# 16P1D_EDA.net
KiCad netlist of a schematic drawn in EasyEDA Pro
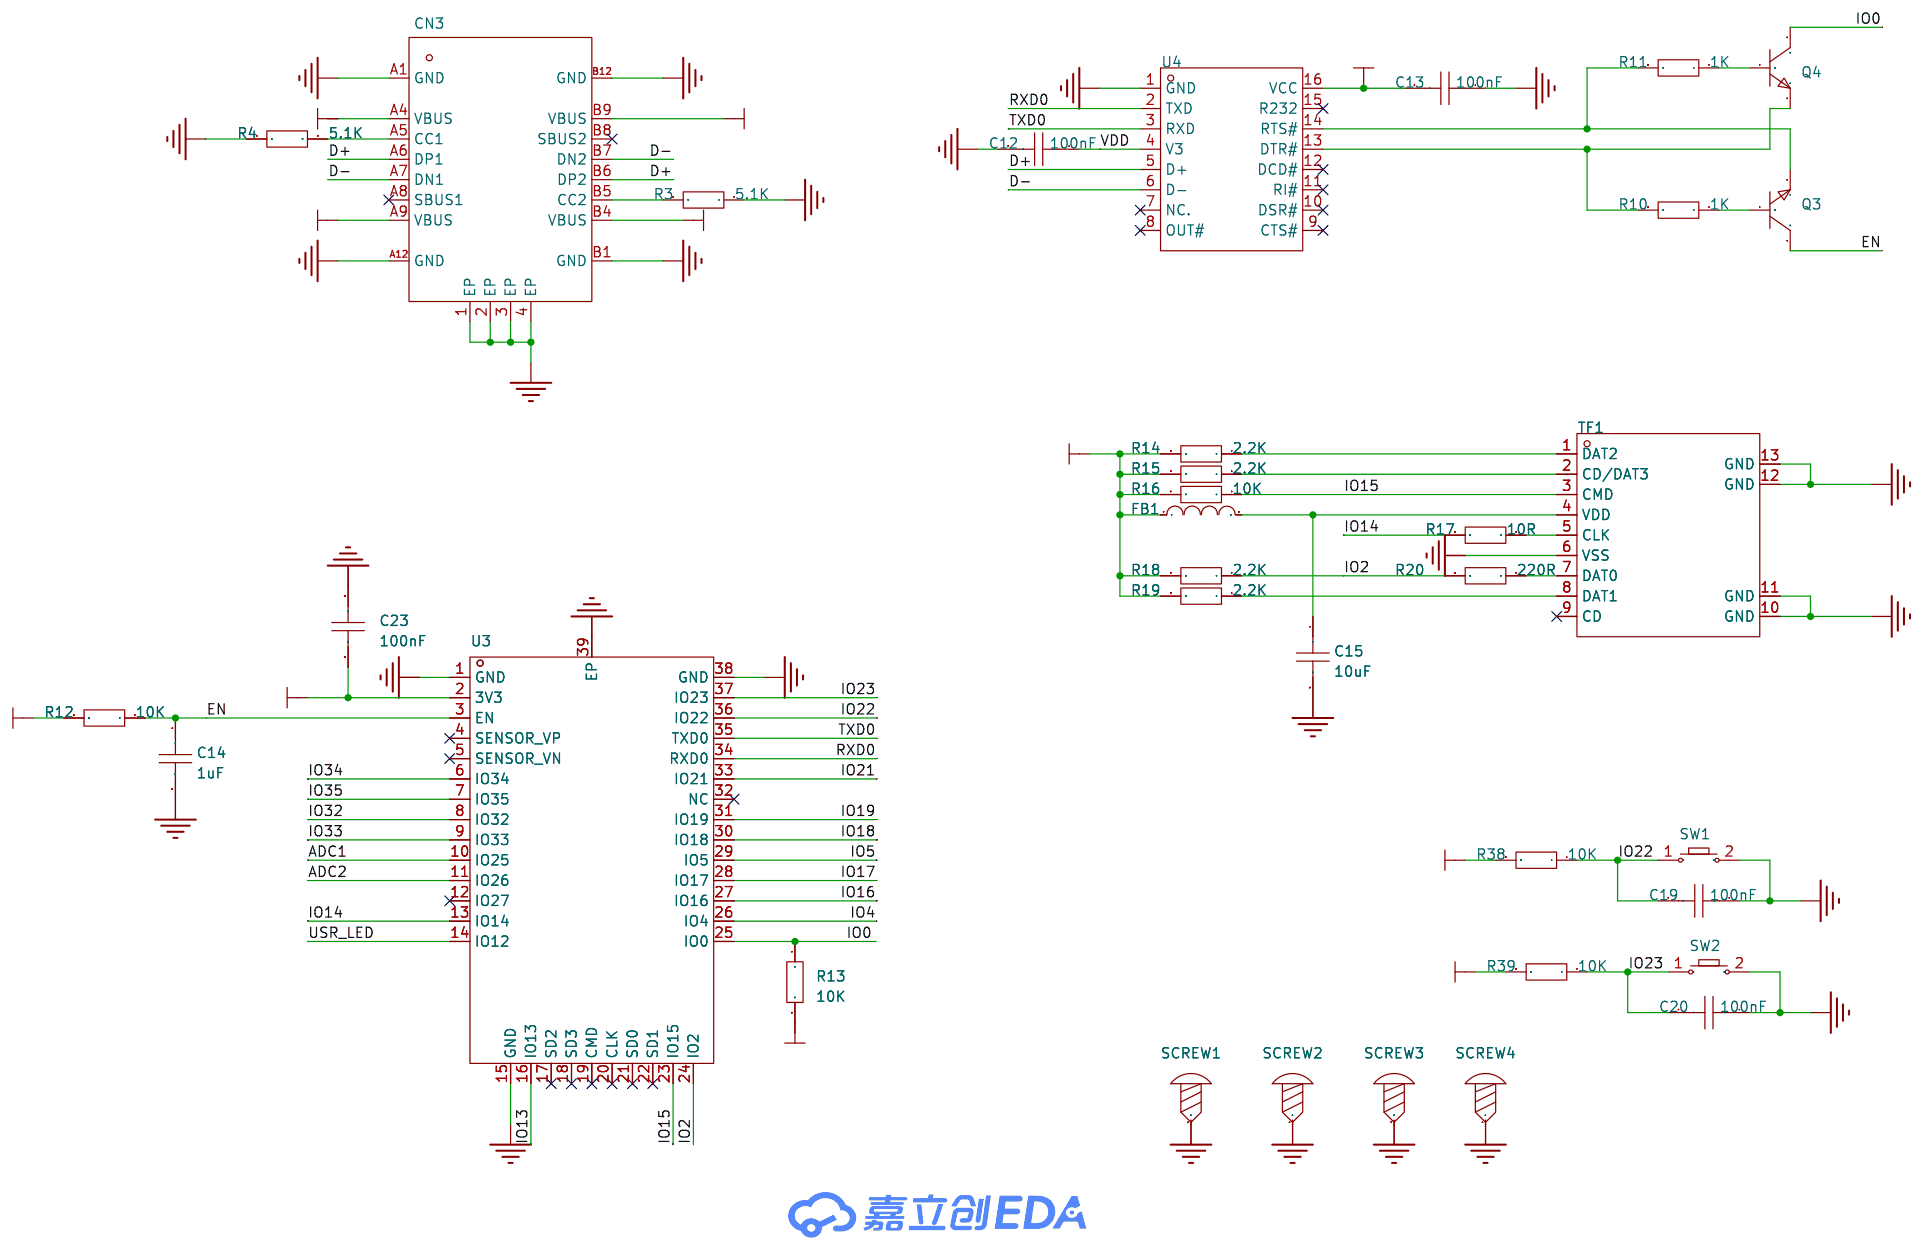
[diagram p0: ESP32]
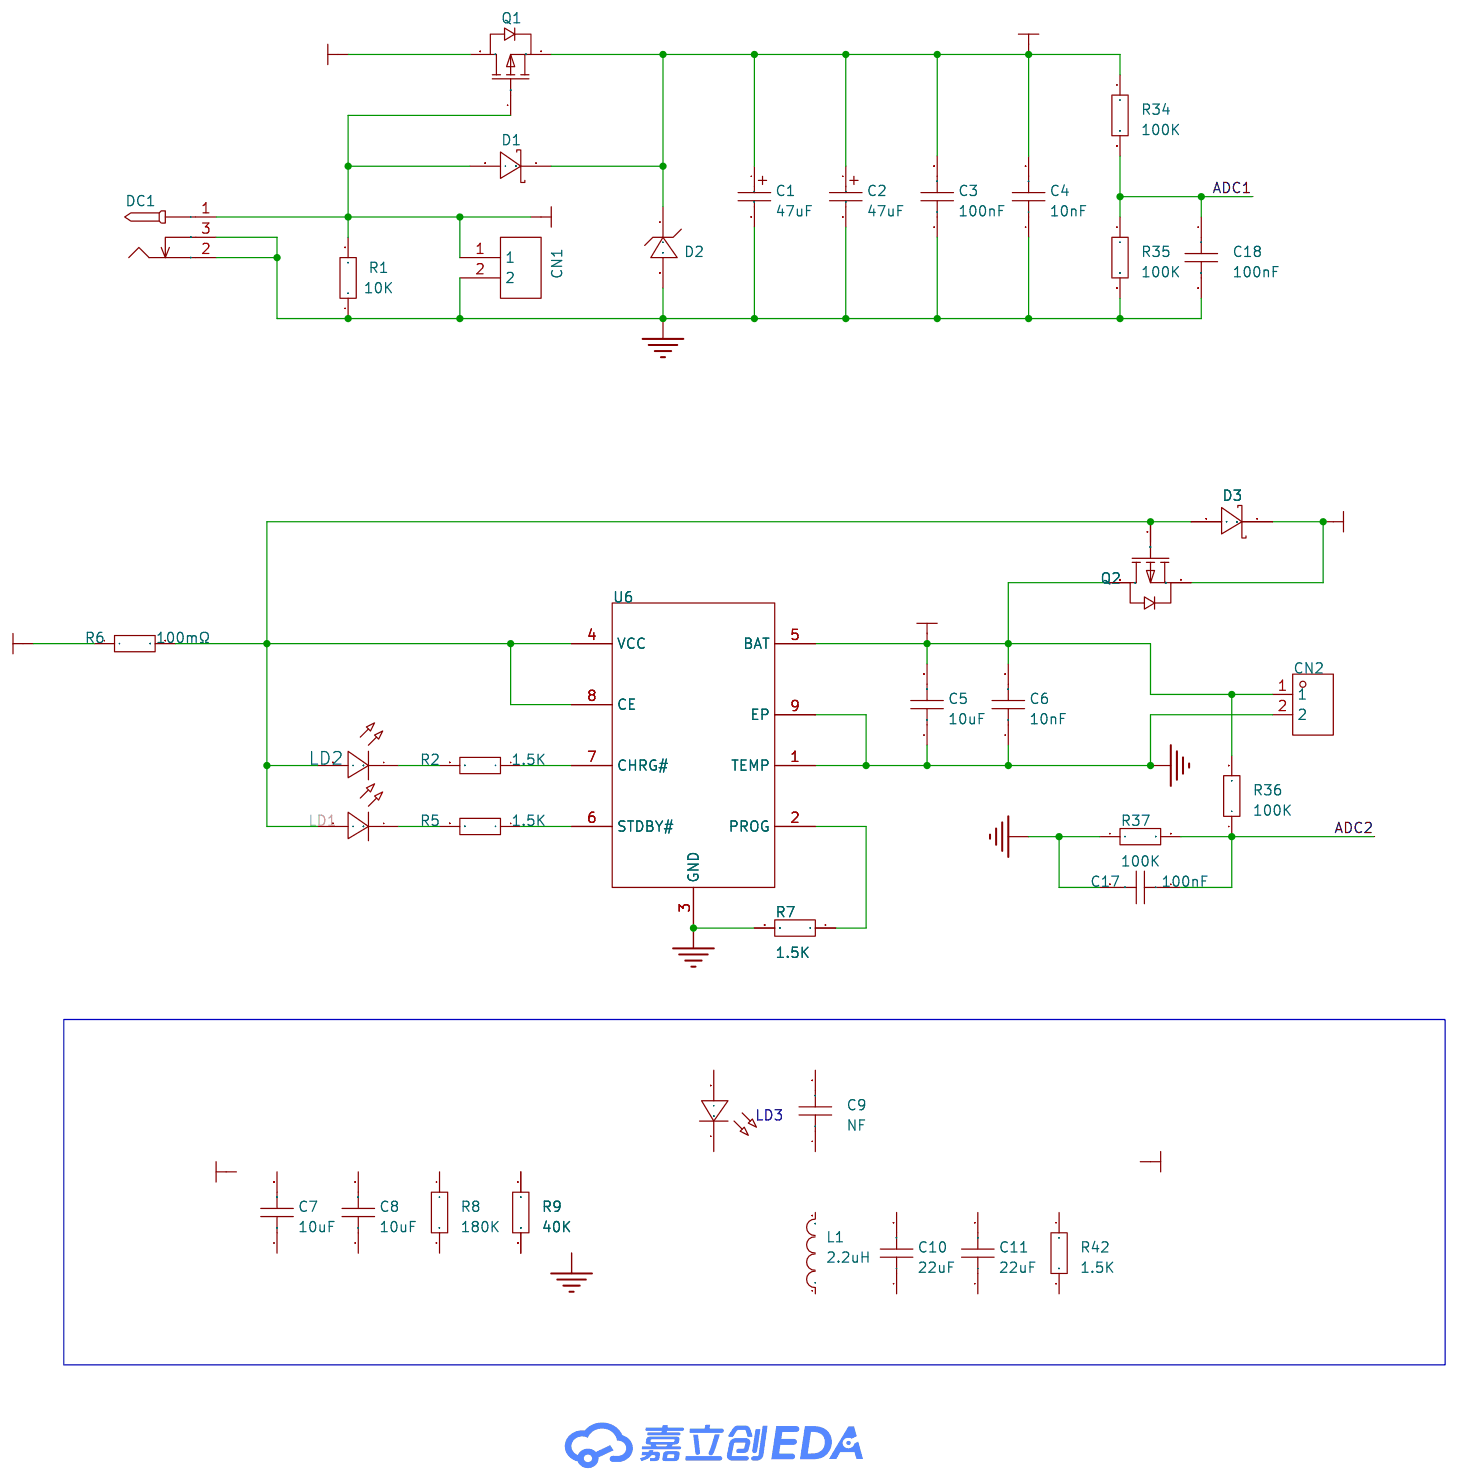
[diagram p1: DC]
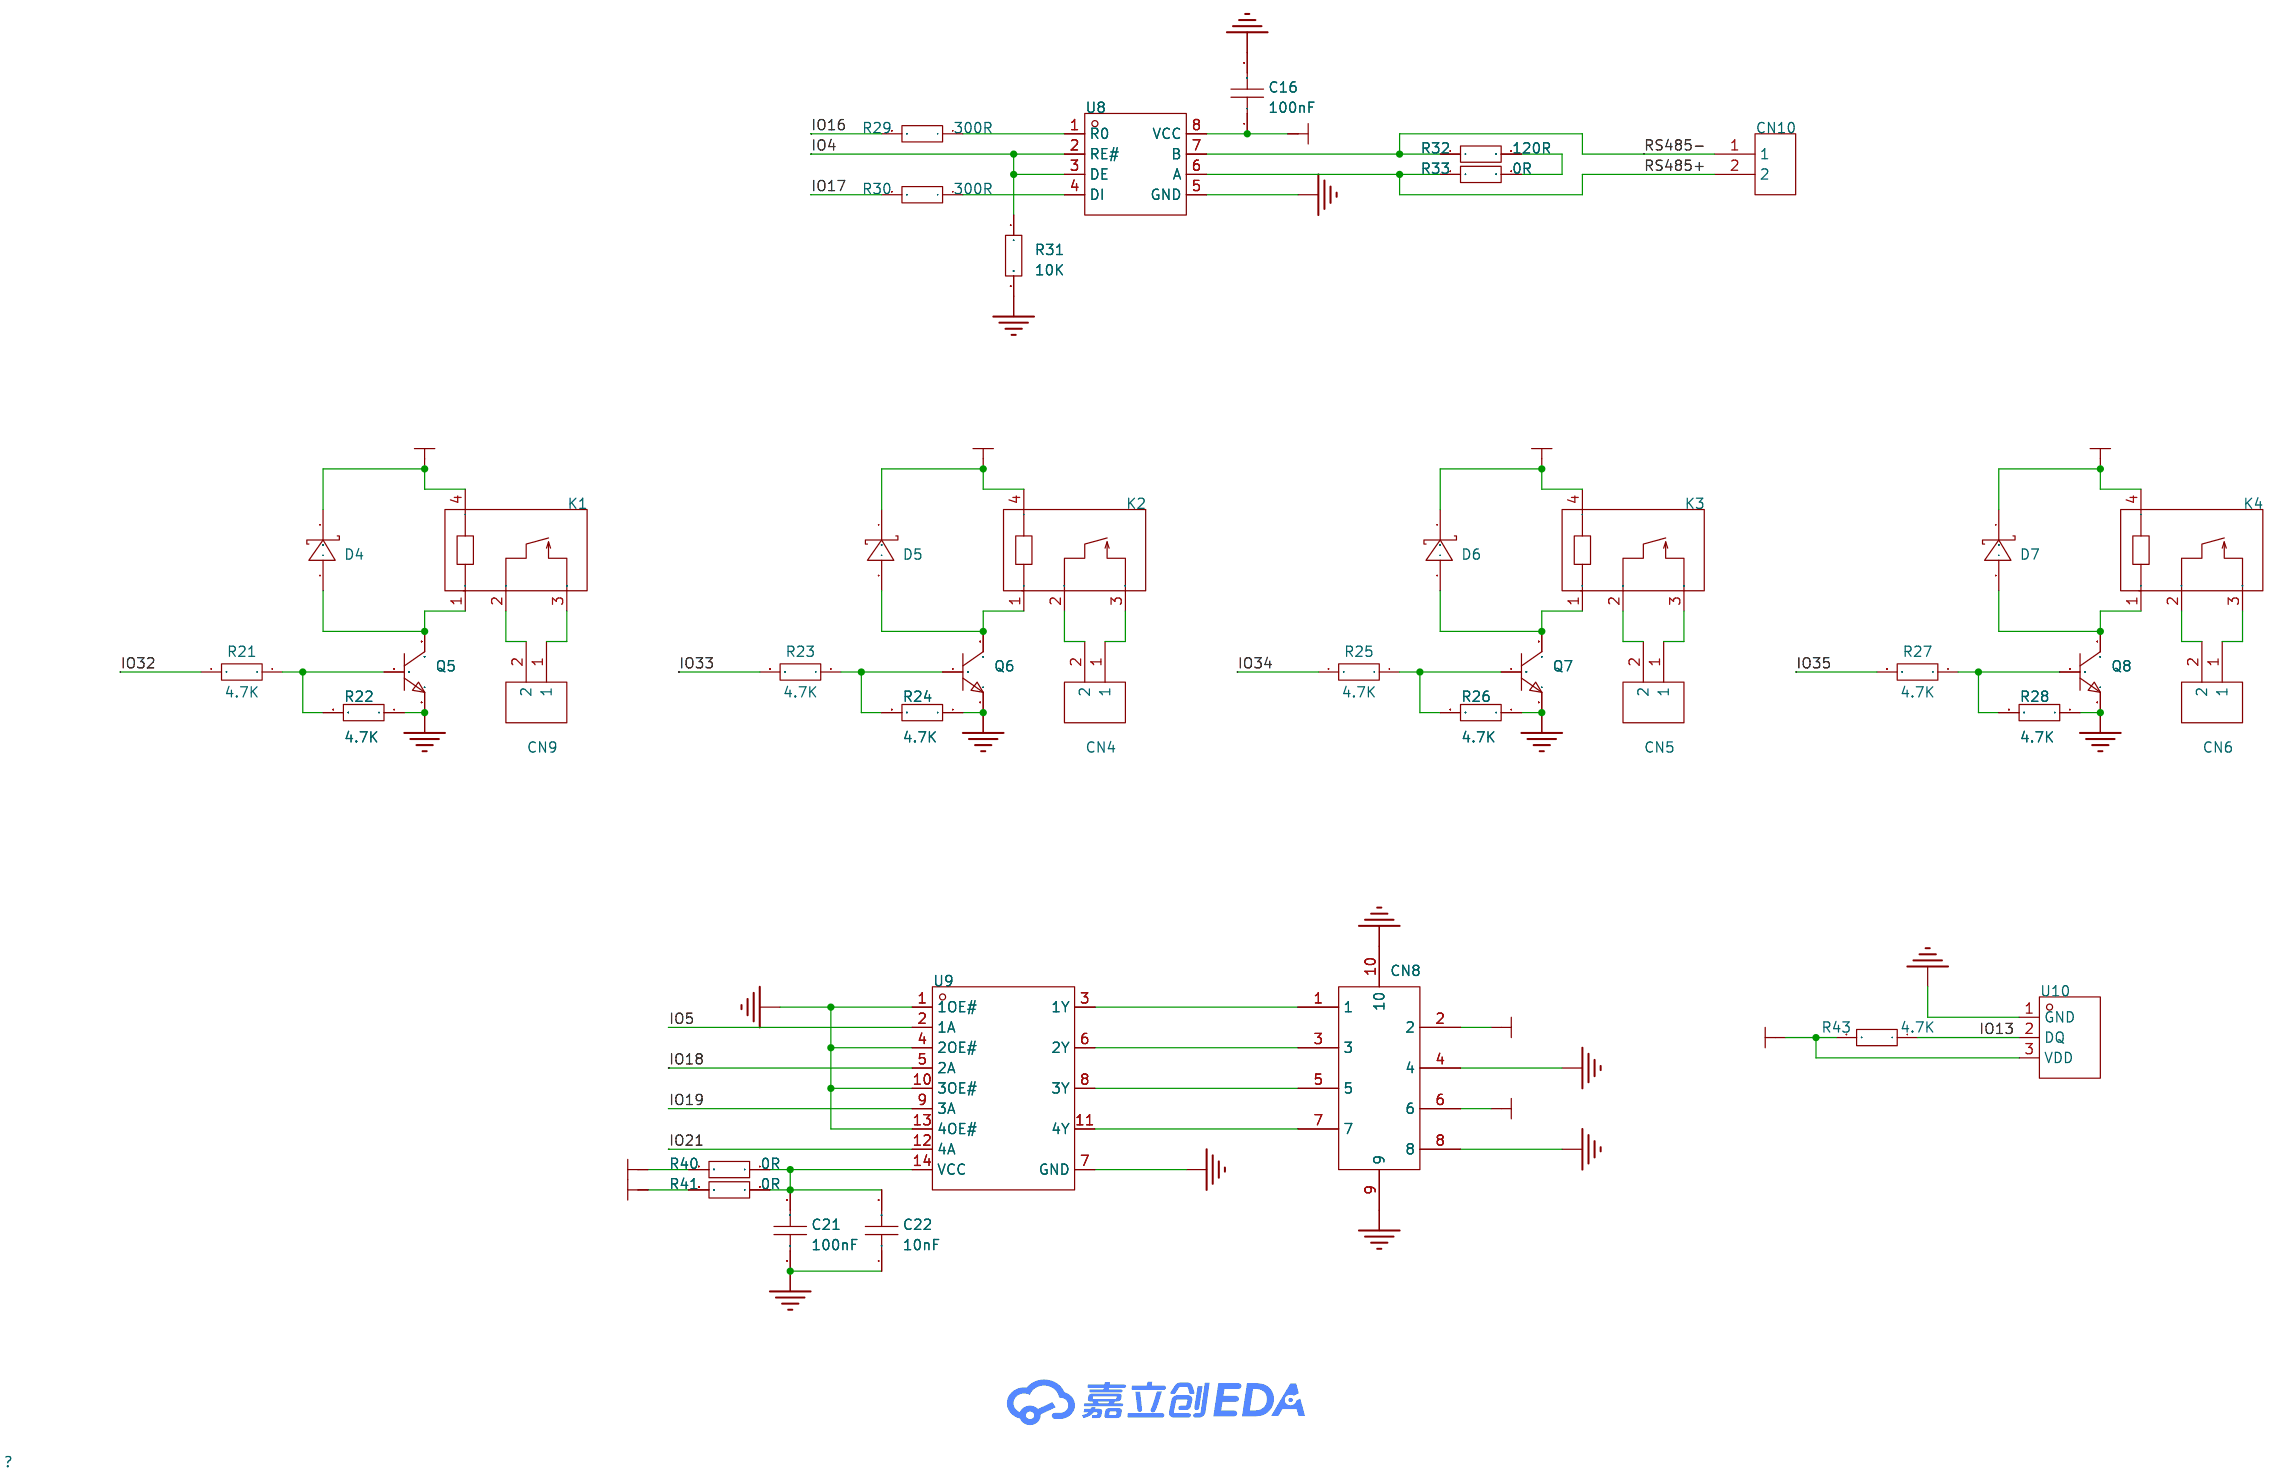
[diagram p2: RELAY]

(export (version "E")
  (design (tool "Eeschema 10.0.6"))
  (components
    (comp (ref "C12")
      (value "100nF")
      (footprint "easyedapro:C0805")
      (libsource (lib "easyedapro") (part "CapAcitance"))
    )
    (comp (ref "C13")
      (value "100nF")
      (footprint "easyedapro:C0805")
      (libsource (lib "easyedapro") (part "CapAcitance"))
    )
    (comp (ref "C14")
      (value "1uF")
      (footprint "easyedapro:C0805")
      (libsource (lib "easyedapro") (part "CapAcitance"))
    )
    (comp (ref "C15")
      (value "10uF")
      (footprint "easyedapro:C0805")
      (libsource (lib "easyedapro") (part "CapAcitance"))
    )
    (comp (ref "C19")
      (value "100nF")
      (footprint "easyedapro:C0805")
      (libsource (lib "easyedapro") (part "CapAcitance"))
    )
    (comp (ref "C20")
      (value "100nF")
      (footprint "easyedapro:C0805")
      (libsource (lib "easyedapro") (part "CapAcitance"))
    )
    (comp (ref "C23")
      (value "100nF")
      (footprint "easyedapro:C0805")
      (libsource (lib "easyedapro") (part "CapAcitance"))
    )
    (comp (ref "CN3")
      (value "~")
      (footprint "easyedapro:USB_TYPE-C-16P")
      (libsource (lib "easyedapro") (part "USB_TYPE-C-16P"))
    )
    (comp (ref "FB1")
      (value "10uH")
      (footprint "easyedapro:L0805")
      (libsource (lib "easyedapro") (part "SDFL2012S100KTF"))
    )
    (comp (ref "Q3")
      (value "SS8050")
      (footprint "easyedapro:SOT-23-3_L2.9-W1.3-P1.90-LS2.4-BR")
      (fields (field (name "Manufacturer") "宏迦橙"))
      (libsource (lib "easyedapro") (part "SS8050_C7420370"))
    )
    (comp (ref "Q4")
      (value "SS8050")
      (footprint "easyedapro:SOT-23-3_L2.9-W1.3-P1.90-LS2.4-BR")
      (fields (field (name "Manufacturer") "宏迦橙"))
      (libsource (lib "easyedapro") (part "SS8050_C7420370"))
    )
    (comp (ref "R3") (value "5.1K") (footprint "easyedapro:R0805") (libsource (lib "easyedapro") (part "电阻")))
    (comp (ref "R4") (value "5.1K") (footprint "easyedapro:R0805") (libsource (lib "easyedapro") (part "电阻")))
    (comp (ref "R10") (value "1K") (footprint "easyedapro:R0805") (libsource (lib "easyedapro") (part "电阻")))
    (comp (ref "R11") (value "1K") (footprint "easyedapro:R0805") (libsource (lib "easyedapro") (part "电阻")))
    (comp (ref "R12") (value "10K") (footprint "easyedapro:R0805") (libsource (lib "easyedapro") (part "电阻")))
    (comp (ref "R13") (value "10K") (footprint "easyedapro:R0805") (libsource (lib "easyedapro") (part "电阻")))
    (comp (ref "R14")
      (value "2.2K")
      (footprint "easyedapro:R0805")
      (libsource (lib "easyedapro") (part "电阻"))
    )
    (comp (ref "R15")
      (value "2.2K")
      (footprint "easyedapro:R0805")
      (libsource (lib "easyedapro") (part "电阻"))
    )
    (comp (ref "R16") (value "10K") (footprint "easyedapro:R0805") (libsource (lib "easyedapro") (part "电阻")))
    (comp (ref "R17") (value "10R") (footprint "easyedapro:R0805") (libsource (lib "easyedapro") (part "电阻")))
    (comp (ref "R18")
      (value "2.2K")
      (footprint "easyedapro:R0805")
      (libsource (lib "easyedapro") (part "电阻"))
    )
    (comp (ref "R19")
      (value "2.2K")
      (footprint "easyedapro:R0805")
      (libsource (lib "easyedapro") (part "电阻"))
    )
    (comp (ref "R20")
      (value "220R")
      (footprint "easyedapro:R0805")
      (libsource (lib "easyedapro") (part "电阻"))
    )
    (comp (ref "R38") (value "10K") (footprint "easyedapro:R0805") (libsource (lib "easyedapro") (part "电阻")))
    (comp (ref "R39") (value "10K") (footprint "easyedapro:R0805") (libsource (lib "easyedapro") (part "电阻")))
    (comp (ref "SCREW1")
      (value "~")
      (footprint "easyedapro:M2螺丝")
      (libsource (lib "easyedapro") (part "螺丝孔"))
    )
    (comp (ref "SCREW2")
      (value "~")
      (footprint "easyedapro:M2螺丝")
      (libsource (lib "easyedapro") (part "螺丝孔"))
    )
    (comp (ref "SCREW3")
      (value "~")
      (footprint "easyedapro:M2螺丝")
      (libsource (lib "easyedapro") (part "螺丝孔"))
    )
    (comp (ref "SCREW4")
      (value "~")
      (footprint "easyedapro:M2螺丝")
      (libsource (lib "easyedapro") (part "螺丝孔"))
    )
    (comp (ref "SW1")
      (value "~")
      (footprint "easyedapro:Key_SMD_3x4x2")
      (libsource (lib "easyedapro") (part "轻触按键x2"))
    )
    (comp (ref "SW2")
      (value "~")
      (footprint "easyedapro:Key_SMD_3x4x2")
      (libsource (lib "easyedapro") (part "轻触按键x2"))
    )
    (comp (ref "TF1")
      (value "TF-CARD H1.8")
      (footprint "easyedapro:TF-SMD_TF-CARD-H1.8")
      (fields (field (name "Manufacturer") "SHOU HAN(首韩)"))
      (libsource (lib "easyedapro") (part "TF-CARD H1.8"))
    )
    (comp (ref "U3")
      (value "ESP32-WROOM-32")
      (footprint "easyedapro:WIFIM-SMD_ESP-WROOM-32")
      (fields (field (name "Manufacturer") "ESPRESSIF(乐鑫)"))
      (libsource (lib "easyedapro") (part "ESP-WROOM-32"))
    )
    (comp (ref "U4")
      (value "CH340C")
      (footprint "easyedapro:SOP-16_L10.0-W3.9-P1.27-LS6.0-BL")
      (fields (field (name "Manufacturer") "WCH(南京沁恒)"))
      (libsource (lib "easyedapro") (part "CH340C"))
    )
    (comp (ref "C1")
      (value "47uF")
      (footprint "easyedapro:C_Ele_SMD_5x5.4mm")
      (libsource (lib "easyedapro") (part "CAP"))
    )
    (comp (ref "C2")
      (value "47uF")
      (footprint "easyedapro:C_Ele_SMD_5x5.4mm")
      (libsource (lib "easyedapro") (part "CAP"))
    )
    (comp (ref "C3")
      (value "100nF")
      (footprint "easyedapro:C0805")
      (libsource (lib "easyedapro") (part "CapAcitance"))
    )
    (comp (ref "C4")
      (value "10nF")
      (footprint "easyedapro:C0805")
      (libsource (lib "easyedapro") (part "CapAcitance"))
    )
    (comp (ref "C5")
      (value "10uF")
      (footprint "easyedapro:C0805")
      (libsource (lib "easyedapro") (part "CapAcitance"))
    )
    (comp (ref "C6")
      (value "10nF")
      (footprint "easyedapro:C0805")
      (libsource (lib "easyedapro") (part "CapAcitance"))
    )
    (comp (ref "C7")
      (value "10uF")
      (footprint "easyedapro:C0805")
      (libsource (lib "easyedapro") (part "CapAcitance"))
    )
    (comp (ref "C8")
      (value "10uF")
      (footprint "easyedapro:C0805")
      (libsource (lib "easyedapro") (part "CapAcitance"))
    )
    (comp (ref "C9")
      (value "NF")
      (footprint "easyedapro:C0805")
      (libsource (lib "easyedapro") (part "CapAcitance"))
    )
    (comp (ref "C10")
      (value "22uF")
      (footprint "easyedapro:C0805")
      (libsource (lib "easyedapro") (part "CapAcitance"))
    )
    (comp (ref "C11")
      (value "22uF")
      (footprint "easyedapro:C0805")
      (libsource (lib "easyedapro") (part "CapAcitance"))
    )
    (comp (ref "C17")
      (value "100nF")
      (footprint "easyedapro:C0805")
      (libsource (lib "easyedapro") (part "CapAcitance"))
    )
    (comp (ref "C18")
      (value "100nF")
      (footprint "easyedapro:C0805")
      (libsource (lib "easyedapro") (part "CapAcitance"))
    )
    (comp (ref "CN1")
      (value "WJ500V-5.08-2P")
      (footprint "easyedapro:CONN-TH_2P-P5.00_WJ500V-5.08-2P")
      (fields (field (name "Manufacturer") "KANGNEX(康奈克斯电气)"))
      (libsource (lib "easyedapro") (part "WJ500V-5.08-2P-14-00A"))
    )
    (comp (ref "CN2")
      (value "ZX-XH2.54-2PZZ")
      (footprint "easyedapro:CONN-TH_2P-P2.50_HX25003-2A")
      (fields (field (name "Manufacturer") "Megastar(兆星)"))
      (libsource (lib "easyedapro") (part "ZX-XH2.54-2PZZ"))
    )
    (comp (ref "D1")
      (value "SS34")
      (footprint "easyedapro:SMC_L6.9-W5.9-LS7.9-RD")
      (fields (field (name "Manufacturer") "onsemi(安森美)"))
      (libsource (lib "easyedapro") (part "SS34_C154551"))
    )
    (comp (ref "D2")
      (value "SMBJ6.0A")
      (footprint "easyedapro:SMB_L4.6-W3.6-LS5.3-RD")
      (fields (field (name "Manufacturer") "RUILON(瑞隆源)"))
      (libsource (lib "easyedapro") (part "SMBJ6.0A_C2987966"))
    )
    (comp (ref "D3")
      (value "SS34")
      (footprint "easyedapro:SMC_L6.9-W5.9-LS7.9-RD")
      (fields (field (name "Manufacturer") "onsemi(安森美)"))
      (libsource (lib "easyedapro") (part "SS34_C154551"))
    )
    (comp (ref "DC1")
      (value "~")
      (footprint "easyedapro:DC-005_2.5")
      (libsource (lib "easyedapro") (part "DC-005_2.5"))
    )
    (comp (ref "L1")
      (value "2.2uH")
      (footprint "easyedapro:IND-SMD_L4.4-W4.2")
      (fields (field (name "Manufacturer Part") "FXL0420-2R2-M") (field (name "Manufacturer") "cjiang(长江微电)"))
      (libsource (lib "easyedapro") (part "FXL0420-2R2-M"))
    )
    (comp (ref "LD1")
      (value "~")
      (footprint "easyedapro:LED_0805")
      (libsource (lib "easyedapro") (part "LED_G"))
    )
    (comp (ref "LD2")
      (value "~")
      (footprint "easyedapro:LED_0805")
      (libsource (lib "easyedapro") (part "LED_R"))
    )
    (comp (ref "LD3")
      (value "~")
      (footprint "easyedapro:LED_0805")
      (libsource (lib "easyedapro") (part "LED_B"))
    )
    (comp (ref "Q1")
      (value "AO3401A")
      (footprint "easyedapro:SOT-23_L2.9-W1.3-P1.90-LS2.4-BR")
      (fields (field (name "Manufacturer") "AOS"))
      (libsource (lib "easyedapro") (part "AO3401A"))
    )
    (comp (ref "Q2")
      (value "AO3401A")
      (footprint "easyedapro:SOT-23_L2.9-W1.3-P1.90-LS2.4-BR")
      (fields (field (name "Manufacturer") "AOS"))
      (libsource (lib "easyedapro") (part "AO3401A"))
    )
    (comp (ref "R1") (value "10K") (footprint "easyedapro:R0805") (libsource (lib "easyedapro") (part "电阻")))
    (comp (ref "R2") (value "1.5K") (footprint "easyedapro:R0805") (libsource (lib "easyedapro") (part "电阻")))
    (comp (ref "R5") (value "1.5K") (footprint "easyedapro:R0805") (libsource (lib "easyedapro") (part "电阻")))
    (comp (ref "R6")
      (value "100mΩ")
      (footprint "easyedapro:R1210")
      (fields
        (field (name "Manufacturer Part") "1210W2F100LT5E")
        (field (name "Manufacturer") "UNI-ROYAL(厚声)")
      )
      (libsource (lib "easyedapro") (part "1210W2F100LT5E"))
    )
    (comp (ref "R7") (value "1.5K") (footprint "easyedapro:R0805") (libsource (lib "easyedapro") (part "电阻")))
    (comp (ref "R8") (value "180K") (footprint "easyedapro:R0805") (libsource (lib "easyedapro") (part "电阻")))
    (comp (ref "R9") (value "40K") (footprint "easyedapro:R0805") (libsource (lib "easyedapro") (part "电阻")))
    (comp (ref "R34")
      (value "100K")
      (footprint "easyedapro:R0805")
      (libsource (lib "easyedapro") (part "电阻"))
    )
    (comp (ref "R35")
      (value "100K")
      (footprint "easyedapro:R0805")
      (libsource (lib "easyedapro") (part "电阻"))
    )
    (comp (ref "R36")
      (value "100K")
      (footprint "easyedapro:R0805")
      (libsource (lib "easyedapro") (part "电阻"))
    )
    (comp (ref "R37")
      (value "100K")
      (footprint "easyedapro:R0805")
      (libsource (lib "easyedapro") (part "电阻"))
    )
    (comp (ref "R42")
      (value "1.5K")
      (footprint "easyedapro:R0805")
      (libsource (lib "easyedapro") (part "电阻"))
    )
    (comp (ref "U6")
      (value "TP4056-42-ESOP8")
      (footprint "easyedapro:ESOP-8_L4.9-W3.9-P1.27-LS6.0-BL-EP")
      (fields (field (name "Manufacturer") "TOPPOWER(南京拓微)"))
      (libsource (lib "easyedapro") (part "TP4056"))
    )
    (comp (ref "C16")
      (value "100nF")
      (footprint "easyedapro:C0805")
      (libsource (lib "easyedapro") (part "CapAcitance"))
    )
    (comp (ref "C21")
      (value "100nF")
      (footprint "easyedapro:C0805")
      (libsource (lib "easyedapro") (part "CapAcitance"))
    )
    (comp (ref "C22")
      (value "10nF")
      (footprint "easyedapro:C0805")
      (libsource (lib "easyedapro") (part "CapAcitance"))
    )
    (comp (ref "CN4")
      (value "WJ500V-5.08-2P")
      (footprint "easyedapro:CONN-TH_2P-P5.00_WJ500V-5.08-2P")
      (fields (field (name "Manufacturer") "KANGNEX(康奈克斯电气)"))
      (libsource (lib "easyedapro") (part "WJ500V-5.08-2P-14-00A"))
    )
    (comp (ref "CN5")
      (value "WJ500V-5.08-2P")
      (footprint "easyedapro:CONN-TH_2P-P5.00_WJ500V-5.08-2P")
      (fields (field (name "Manufacturer") "KANGNEX(康奈克斯电气)"))
      (libsource (lib "easyedapro") (part "WJ500V-5.08-2P-14-00A"))
    )
    (comp (ref "CN6")
      (value "WJ500V-5.08-2P")
      (footprint "easyedapro:CONN-TH_2P-P5.00_WJ500V-5.08-2P")
      (fields (field (name "Manufacturer") "KANGNEX(康奈克斯电气)"))
      (libsource (lib "easyedapro") (part "WJ500V-5.08-2P-14-00A"))
    )
    (comp (ref "CN8")
      (value "8P-立贴带锁")
      (footprint "easyedapro:FPC-SMD_8P-P0.50_AFC11-S08ICC-00")
      (libsource (lib "easyedapro") (part "8P-立贴带锁"))
    )
    (comp (ref "CN9")
      (value "WJ500V-5.08-2P")
      (footprint "easyedapro:CONN-TH_2P-P5.00_WJ500V-5.08-2P")
      (fields (field (name "Manufacturer") "KANGNEX(康奈克斯电气)"))
      (libsource (lib "easyedapro") (part "WJ500V-5.08-2P-14-00A"))
    )
    (comp (ref "CN10")
      (value "WJ500V-5.08-2P")
      (footprint "easyedapro:CONN-TH_2P-P5.00_WJ500V-5.08-2P")
      (fields (field (name "Manufacturer") "KANGNEX(康奈克斯电气)"))
      (libsource (lib "easyedapro") (part "WJ500V-5.08-2P-14-00A"))
    )
    (comp (ref "D4")
      (value "SS34")
      (footprint "easyedapro:SMC_L6.9-W5.9-LS7.9-RD")
      (fields (field (name "Manufacturer") "onsemi(安森美)"))
      (libsource (lib "easyedapro") (part "SS34_C154551"))
    )
    (comp (ref "D5")
      (value "SS34")
      (footprint "easyedapro:SMC_L6.9-W5.9-LS7.9-RD")
      (fields (field (name "Manufacturer") "onsemi(安森美)"))
      (libsource (lib "easyedapro") (part "SS34_C154551"))
    )
    (comp (ref "D6")
      (value "SS34")
      (footprint "easyedapro:SMC_L6.9-W5.9-LS7.9-RD")
      (fields (field (name "Manufacturer") "onsemi(安森美)"))
      (libsource (lib "easyedapro") (part "SS34_C154551"))
    )
    (comp (ref "D7")
      (value "SS34")
      (footprint "easyedapro:SMC_L6.9-W5.9-LS7.9-RD")
      (fields (field (name "Manufacturer") "onsemi(安森美)"))
      (libsource (lib "easyedapro") (part "SS34_C154551"))
    )
    (comp (ref "K1")
      (value "G5NB-1A-E-12VDC")
      (footprint "easyedapro:RELAY-TH_G5NB-1A-E-DCXX")
      (libsource (lib "easyedapro") (part "G5NB-1A-E-12VDC"))
    )
    (comp (ref "K2")
      (value "G5NB-1A-E-12VDC")
      (footprint "easyedapro:RELAY-TH_G5NB-1A-E-DCXX")
      (libsource (lib "easyedapro") (part "G5NB-1A-E-12VDC"))
    )
    (comp (ref "K3")
      (value "G5NB-1A-E-12VDC")
      (footprint "easyedapro:RELAY-TH_G5NB-1A-E-DCXX")
      (libsource (lib "easyedapro") (part "G5NB-1A-E-12VDC"))
    )
    (comp (ref "K4")
      (value "G5NB-1A-E-12VDC")
      (footprint "easyedapro:RELAY-TH_G5NB-1A-E-DCXX")
      (libsource (lib "easyedapro") (part "G5NB-1A-E-12VDC"))
    )
    (comp (ref "Q5")
      (value "SS8050")
      (footprint "easyedapro:SOT-23-3_L2.9-W1.3-P1.90-LS2.4-BR")
      (fields (field (name "Manufacturer") "宏迦橙"))
      (libsource (lib "easyedapro") (part "SS8050_C7420370"))
    )
    (comp (ref "Q6")
      (value "SS8050")
      (footprint "easyedapro:SOT-23-3_L2.9-W1.3-P1.90-LS2.4-BR")
      (fields (field (name "Manufacturer") "宏迦橙"))
      (libsource (lib "easyedapro") (part "SS8050_C7420370"))
    )
    (comp (ref "Q7")
      (value "SS8050")
      (footprint "easyedapro:SOT-23-3_L2.9-W1.3-P1.90-LS2.4-BR")
      (fields (field (name "Manufacturer") "宏迦橙"))
      (libsource (lib "easyedapro") (part "SS8050_C7420370"))
    )
    (comp (ref "Q8")
      (value "SS8050")
      (footprint "easyedapro:SOT-23-3_L2.9-W1.3-P1.90-LS2.4-BR")
      (fields (field (name "Manufacturer") "宏迦橙"))
      (libsource (lib "easyedapro") (part "SS8050_C7420370"))
    )
    (comp (ref "R21")
      (value "4.7K")
      (footprint "easyedapro:R0805")
      (libsource (lib "easyedapro") (part "电阻"))
    )
    (comp (ref "R22")
      (value "4.7K")
      (footprint "easyedapro:R0805")
      (libsource (lib "easyedapro") (part "电阻"))
    )
    (comp (ref "R23")
      (value "4.7K")
      (footprint "easyedapro:R0805")
      (libsource (lib "easyedapro") (part "电阻"))
    )
    (comp (ref "R24")
      (value "4.7K")
      (footprint "easyedapro:R0805")
      (libsource (lib "easyedapro") (part "电阻"))
    )
    (comp (ref "R25")
      (value "4.7K")
      (footprint "easyedapro:R0805")
      (libsource (lib "easyedapro") (part "电阻"))
    )
    (comp (ref "R26")
      (value "4.7K")
      (footprint "easyedapro:R0805")
      (libsource (lib "easyedapro") (part "电阻"))
    )
    (comp (ref "R27")
      (value "4.7K")
      (footprint "easyedapro:R0805")
      (libsource (lib "easyedapro") (part "电阻"))
    )
    (comp (ref "R28")
      (value "4.7K")
      (footprint "easyedapro:R0805")
      (libsource (lib "easyedapro") (part "电阻"))
    )
    (comp (ref "R29")
      (value "300R")
      (footprint "easyedapro:R0805")
      (libsource (lib "easyedapro") (part "电阻"))
    )
    (comp (ref "R30")
      (value "300R")
      (footprint "easyedapro:R0805")
      (libsource (lib "easyedapro") (part "电阻"))
    )
    (comp (ref "R31") (value "10K") (footprint "easyedapro:R0805") (libsource (lib "easyedapro") (part "电阻")))
    (comp (ref "R32")
      (value "120R")
      (footprint "easyedapro:R0805")
      (libsource (lib "easyedapro") (part "电阻"))
    )
    (comp (ref "R33") (value "0R") (footprint "easyedapro:R0805") (libsource (lib "easyedapro") (part "电阻")))
    (comp (ref "R40") (value "0R") (footprint "easyedapro:R0805") (libsource (lib "easyedapro") (part "电阻")))
    (comp (ref "R41") (value "0R") (footprint "easyedapro:R0805") (libsource (lib "easyedapro") (part "电阻")))
    (comp (ref "R43")
      (value "4.7K")
      (footprint "easyedapro:R0805")
      (libsource (lib "easyedapro") (part "电阻"))
    )
    (comp (ref "U8")
      (value "MAX485EIM/TR")
      (footprint "easyedapro:SOP-8_L4.9-W3.9-P1.27-LS6.0-BL")
      (fields (field (name "Manufacturer") "HGSEMI(华冠)"))
      (libsource (lib "easyedapro") (part "MAX485EIM/TR"))
    )
    (comp (ref "U9")
      (value "74HC125D/S400118")
      (footprint "easyedapro:SOIC-14_L8.6-W3.8-P1.27-LS6.0-BL")
      (fields (field (name "Manufacturer") "Nexperia(安世)"))
      (libsource (lib "easyedapro") (part "74HC125D/S400118"))
    )
    (comp (ref "U10")
      (value "GX18B20")
      (footprint "easyedapro:TO-92-3_L4.9-W3.7-P1.27-L")
      (fields (field (name "Manufacturer") "GXCAS(中科银河芯)"))
      (libsource (lib "easyedapro") (part "GX18B20"))
    )
  )
  (nets
    (net (code "1") (name "ADC1") (class "Default")
      (node (ref "C18") (pin "1") (pinfunction "1_1") (pintype "input"))
      (node (ref "R34") (pin "2") (pinfunction "2_2") (pintype "input"))
      (node (ref "R35") (pin "1") (pinfunction "1_1") (pintype "input"))
      (node (ref "U3") (pin "10") (pinfunction "IO25_10") (pintype "unspecified"))
    )
    (net (code "2") (name "ADC2") (class "Default")
      (node (ref "C17") (pin "1") (pinfunction "1_1") (pintype "input"))
      (node (ref "R36") (pin "1") (pinfunction "1_1") (pintype "input"))
      (node (ref "R37") (pin "2") (pinfunction "2_2") (pintype "input"))
      (node (ref "U3") (pin "11") (pinfunction "IO26_11") (pintype "unspecified"))
    )
    (net (code "3") (name "D+") (class "Default")
      (node (ref "CN3") (pin "A6") (pinfunction "DP1_A6") (pintype "input"))
      (node (ref "CN3") (pin "B6") (pinfunction "DP2_B6") (pintype "input"))
      (node (ref "U4") (pin "5") (pinfunction "D+_5") (pintype "unspecified"))
    )
    (net (code "4") (name "D-") (class "Default")
      (node (ref "CN3") (pin "A7") (pinfunction "DN1_A7") (pintype "input"))
      (node (ref "CN3") (pin "B7") (pinfunction "DN2_B7") (pintype "input"))
      (node (ref "U4") (pin "6") (pinfunction "D-_6") (pintype "unspecified"))
    )
    (net (code "5") (name "EN") (class "Default")
      (node (ref "C14") (pin "1") (pinfunction "1_1") (pintype "input"))
      (node (ref "Q3") (pin "3") (pinfunction "C_3") (pintype "input"))
      (node (ref "R12") (pin "1") (pinfunction "1_1") (pintype "input"))
      (node (ref "U3") (pin "3") (pinfunction "EN_3") (pintype "unspecified"))
    )
    (net (code "6") (name "GND") (class "Default")
      (node (ref "C1") (pin "2") (pinfunction "2_2") (pintype "input"))
      (node (ref "C12") (pin "2") (pinfunction "2_2") (pintype "input"))
      (node (ref "C13") (pin "1") (pinfunction "1_1") (pintype "input"))
      (node (ref "C14") (pin "2") (pinfunction "2_2") (pintype "input"))
      (node (ref "C15") (pin "2") (pinfunction "2_2") (pintype "input"))
      (node (ref "C16") (pin "2") (pinfunction "2_2") (pintype "input"))
      (node (ref "C17") (pin "2") (pinfunction "2_2") (pintype "input"))
      (node (ref "C18") (pin "2") (pinfunction "2_2") (pintype "input"))
      (node (ref "C19") (pin "1") (pinfunction "1_1") (pintype "input"))
      (node (ref "C2") (pin "2") (pinfunction "2_2") (pintype "input"))
      (node (ref "C20") (pin "1") (pinfunction "1_1") (pintype "input"))
      (node (ref "C21") (pin "1") (pinfunction "1_1") (pintype "input"))
      (node (ref "C22") (pin "1") (pinfunction "1_1") (pintype "input"))
      (node (ref "C23") (pin "2") (pinfunction "2_2") (pintype "input"))
      (node (ref "C3") (pin "1") (pinfunction "1_1") (pintype "input"))
      (node (ref "C4") (pin "1") (pinfunction "1_1") (pintype "input"))
      (node (ref "C5") (pin "1") (pinfunction "1_1") (pintype "input"))
      (node (ref "C6") (pin "1") (pinfunction "1_1") (pintype "input"))
      (node (ref "CN1") (pin "2") (pinfunction "2_2") (pintype "unspecified"))
      (node (ref "CN2") (pin "2") (pinfunction "2_2") (pintype "unspecified"))
      (node (ref "CN3") (pin "1") (pinfunction "EP_1") (pintype "input"))
      (node (ref "CN3") (pin "2") (pinfunction "EP_2") (pintype "input"))
      (node (ref "CN3") (pin "3") (pinfunction "EP_3") (pintype "input"))
      (node (ref "CN3") (pin "4") (pinfunction "EP_4") (pintype "input"))
      (node (ref "CN3") (pin "A1") (pinfunction "GND_A1") (pintype "input"))
      (node (ref "CN3") (pin "A12") (pinfunction "GND_A12") (pintype "input"))
      (node (ref "CN3") (pin "B1") (pinfunction "GND_B1") (pintype "input"))
      (node (ref "CN3") (pin "B12") (pinfunction "GND_B12") (pintype "input"))
      (node (ref "CN8") (pin "10") (pinfunction "10_10") (pintype "unspecified"))
      (node (ref "CN8") (pin "4") (pinfunction "4_4") (pintype "unspecified"))
      (node (ref "CN8") (pin "8") (pinfunction "8_8") (pintype "unspecified"))
      (node (ref "CN8") (pin "9") (pinfunction "9_9") (pintype "unspecified"))
      (node (ref "D2") (pin "2") (pinfunction "2_2") (pintype "unspecified"))
      (node (ref "DC1") (pin "2") (pinfunction "2_2") (pintype "input"))
      (node (ref "DC1") (pin "3") (pinfunction "3_3") (pintype "input"))
      (node (ref "Q5") (pin "2") (pinfunction "E_2") (pintype "input"))
      (node (ref "Q6") (pin "2") (pinfunction "E_2") (pintype "input"))
      (node (ref "Q7") (pin "2") (pinfunction "E_2") (pintype "input"))
      (node (ref "Q8") (pin "2") (pinfunction "E_2") (pintype "input"))
      (node (ref "R1") (pin "1") (pinfunction "1_1") (pintype "input"))
      (node (ref "R22") (pin "1") (pinfunction "1_1") (pintype "input"))
      (node (ref "R24") (pin "1") (pinfunction "1_1") (pintype "input"))
      (node (ref "R26") (pin "1") (pinfunction "1_1") (pintype "input"))
      (node (ref "R28") (pin "1") (pinfunction "1_1") (pintype "input"))
      (node (ref "R3") (pin "1") (pinfunction "1_1") (pintype "input"))
      (node (ref "R31") (pin "2") (pinfunction "2_2") (pintype "input"))
      (node (ref "R35") (pin "2") (pinfunction "2_2") (pintype "input"))
      (node (ref "R37") (pin "1") (pinfunction "1_1") (pintype "input"))
      (node (ref "R4") (pin "1") (pinfunction "1_1") (pintype "input"))
      (node (ref "R7") (pin "2") (pinfunction "2_2") (pintype "input"))
      (node (ref "SCREW1") (pin "1") (pinfunction "1_1") (pintype "input"))
      (node (ref "SCREW2") (pin "1") (pinfunction "1_1") (pintype "input"))
      (node (ref "SCREW3") (pin "1") (pinfunction "1_1") (pintype "input"))
      (node (ref "SCREW4") (pin "1") (pinfunction "1_1") (pintype "input"))
      (node (ref "SW1") (pin "2") (pinfunction "2_2") (pintype "input"))
      (node (ref "SW2") (pin "2") (pinfunction "2_2") (pintype "input"))
      (node (ref "TF1") (pin "10") (pinfunction "GND_10") (pintype "unspecified"))
      (node (ref "TF1") (pin "11") (pinfunction "GND_11") (pintype "unspecified"))
      (node (ref "TF1") (pin "12") (pinfunction "GND_12") (pintype "unspecified"))
      (node (ref "TF1") (pin "13") (pinfunction "GND_13") (pintype "unspecified"))
      (node (ref "TF1") (pin "6") (pinfunction "VSS_6") (pintype "unspecified"))
      (node (ref "U10") (pin "1") (pinfunction "GND_1") (pintype "input"))
      (node (ref "U3") (pin "1") (pinfunction "GND_1") (pintype "unspecified"))
      (node (ref "U3") (pin "15") (pinfunction "GND_15") (pintype "unspecified"))
      (node (ref "U3") (pin "38") (pinfunction "GND_38") (pintype "unspecified"))
      (node (ref "U3") (pin "39") (pinfunction "EP_39") (pintype "unspecified"))
      (node (ref "U4") (pin "1") (pinfunction "GND_1") (pintype "unspecified"))
      (node (ref "U6") (pin "1") (pinfunction "TEMP_1") (pintype "unspecified"))
      (node (ref "U6") (pin "3") (pinfunction "GND_3") (pintype "unspecified"))
      (node (ref "U6") (pin "9") (pinfunction "EP_9") (pintype "unspecified"))
      (node (ref "U8") (pin "5") (pinfunction "GND_5") (pintype "unspecified"))
      (node (ref "U9") (pin "1") (pinfunction "1OE#_1") (pintype "unspecified"))
      (node (ref "U9") (pin "10") (pinfunction "3OE#_10") (pintype "unspecified"))
      (node (ref "U9") (pin "13") (pinfunction "4OE#_13") (pintype "unspecified"))
      (node (ref "U9") (pin "4") (pinfunction "2OE#_4") (pintype "unspecified"))
      (node (ref "U9") (pin "7") (pinfunction "GND_7") (pintype "unspecified"))
    )
    (net (code "7") (name "IO0") (class "Default")
      (node (ref "Q4") (pin "3") (pinfunction "C_3") (pintype "input"))
      (node (ref "R13") (pin "1") (pinfunction "1_1") (pintype "input"))
      (node (ref "U3") (pin "25") (pinfunction "IO0_25") (pintype "unspecified"))
    )
    (net (code "8") (name "IO2") (class "Default")
      (node (ref "R18") (pin "1") (pinfunction "1_1") (pintype "input"))
      (node (ref "R20") (pin "2") (pinfunction "2_2") (pintype "input"))
      (node (ref "U3") (pin "24") (pinfunction "IO2_24") (pintype "unspecified"))
    )
    (net (code "9") (name "IO4") (class "Default")
      (node (ref "R31") (pin "1") (pinfunction "1_1") (pintype "input"))
      (node (ref "U3") (pin "26") (pinfunction "IO4_26") (pintype "unspecified"))
      (node (ref "U8") (pin "2") (pinfunction "RE#_2") (pintype "unspecified"))
      (node (ref "U8") (pin "3") (pinfunction "DE_3") (pintype "unspecified"))
    )
    (net (code "10") (name "IO5") (class "Default")
      (node (ref "U3") (pin "29") (pinfunction "IO5_29") (pintype "unspecified"))
      (node (ref "U9") (pin "2") (pinfunction "1A_2") (pintype "unspecified"))
    )
    (net (code "11") (name "IO13") (class "Default")
      (node (ref "R43") (pin "1") (pinfunction "1_1") (pintype "input"))
      (node (ref "U10") (pin "2") (pinfunction "DQ_2") (pintype "input"))
      (node (ref "U3") (pin "16") (pinfunction "IO13_16") (pintype "unspecified"))
    )
    (net (code "12") (name "IO14") (class "Default")
      (node (ref "R17") (pin "2") (pinfunction "2_2") (pintype "input"))
      (node (ref "U3") (pin "13") (pinfunction "IO14_13") (pintype "unspecified"))
    )
    (net (code "13") (name "IO15") (class "Default")
      (node (ref "R16") (pin "1") (pinfunction "1_1") (pintype "input"))
      (node (ref "TF1") (pin "3") (pinfunction "CMD_3") (pintype "unspecified"))
      (node (ref "U3") (pin "23") (pinfunction "IO15_23") (pintype "unspecified"))
    )
    (net (code "14") (name "IO16") (class "Default")
      (node (ref "R29") (pin "2") (pinfunction "2_2") (pintype "input"))
      (node (ref "U3") (pin "27") (pinfunction "IO16_27") (pintype "unspecified"))
    )
    (net (code "15") (name "IO17") (class "Default")
      (node (ref "R30") (pin "2") (pinfunction "2_2") (pintype "input"))
      (node (ref "U3") (pin "28") (pinfunction "IO17_28") (pintype "unspecified"))
    )
    (net (code "16") (name "IO18") (class "Default")
      (node (ref "U3") (pin "30") (pinfunction "IO18_30") (pintype "unspecified"))
      (node (ref "U9") (pin "5") (pinfunction "2A_5") (pintype "unspecified"))
    )
    (net (code "17") (name "IO19") (class "Default")
      (node (ref "U3") (pin "31") (pinfunction "IO19_31") (pintype "unspecified"))
      (node (ref "U9") (pin "9") (pinfunction "3A_9") (pintype "unspecified"))
    )
    (net (code "18") (name "IO21") (class "Default")
      (node (ref "U3") (pin "33") (pinfunction "IO21_33") (pintype "unspecified"))
      (node (ref "U9") (pin "12") (pinfunction "4A_12") (pintype "unspecified"))
    )
    (net (code "19") (name "IO22") (class "Default")
      (node (ref "C19") (pin "2") (pinfunction "2_2") (pintype "input"))
      (node (ref "R38") (pin "1") (pinfunction "1_1") (pintype "input"))
      (node (ref "SW1") (pin "1") (pinfunction "1_1") (pintype "input"))
      (node (ref "U3") (pin "36") (pinfunction "IO22_36") (pintype "unspecified"))
    )
    (net (code "20") (name "IO23") (class "Default")
      (node (ref "C20") (pin "2") (pinfunction "2_2") (pintype "input"))
      (node (ref "R39") (pin "1") (pinfunction "1_1") (pintype "input"))
      (node (ref "SW2") (pin "1") (pinfunction "1_1") (pintype "input"))
      (node (ref "U3") (pin "37") (pinfunction "IO23_37") (pintype "unspecified"))
    )
    (net (code "21") (name "IO32") (class "Default")
      (node (ref "R21") (pin "2") (pinfunction "2_2") (pintype "input"))
      (node (ref "U3") (pin "8") (pinfunction "IO32_8") (pintype "unspecified"))
    )
    (net (code "22") (name "IO33") (class "Default")
      (node (ref "R23") (pin "2") (pinfunction "2_2") (pintype "input"))
      (node (ref "U3") (pin "9") (pinfunction "IO33_9") (pintype "unspecified"))
    )
    (net (code "23") (name "IO34") (class "Default")
      (node (ref "R25") (pin "2") (pinfunction "2_2") (pintype "input"))
      (node (ref "U3") (pin "6") (pinfunction "IO34_6") (pintype "unspecified"))
    )
    (net (code "24") (name "IO35") (class "Default")
      (node (ref "R27") (pin "2") (pinfunction "2_2") (pintype "input"))
      (node (ref "U3") (pin "7") (pinfunction "IO35_7") (pintype "unspecified"))
    )
    (net (code "25") (name "Net-(CN3-CC1)") (class "Default")
      (node (ref "CN3") (pin "A5") (pinfunction "CC1_A5") (pintype "input"))
      (node (ref "R4") (pin "2") (pinfunction "2_2") (pintype "input"))
    )
    (net (code "26") (name "Net-(CN3-CC2)") (class "Default")
      (node (ref "CN3") (pin "B5") (pinfunction "CC2_B5") (pintype "input"))
      (node (ref "R3") (pin "2") (pinfunction "2_2") (pintype "input"))
    )
    (net (code "27") (name "Net-(CN4-Pad1)") (class "Default")
      (node (ref "CN4") (pin "1") (pinfunction "1_1") (pintype "unspecified"))
      (node (ref "K2") (pin "3") (pinfunction "3_3") (pintype "unspecified"))
    )
    (net (code "28") (name "Net-(CN4-Pad2)") (class "Default")
      (node (ref "CN4") (pin "2") (pinfunction "2_2") (pintype "unspecified"))
      (node (ref "K2") (pin "2") (pinfunction "2_2") (pintype "unspecified"))
    )
    (net (code "29") (name "Net-(CN5-Pad1)") (class "Default")
      (node (ref "CN5") (pin "1") (pinfunction "1_1") (pintype "unspecified"))
      (node (ref "K3") (pin "3") (pinfunction "3_3") (pintype "unspecified"))
    )
    (net (code "30") (name "Net-(CN5-Pad2)") (class "Default")
      (node (ref "CN5") (pin "2") (pinfunction "2_2") (pintype "unspecified"))
      (node (ref "K3") (pin "2") (pinfunction "2_2") (pintype "unspecified"))
    )
    (net (code "31") (name "Net-(CN6-Pad1)") (class "Default")
      (node (ref "CN6") (pin "1") (pinfunction "1_1") (pintype "unspecified"))
      (node (ref "K4") (pin "3") (pinfunction "3_3") (pintype "unspecified"))
    )
    (net (code "32") (name "Net-(CN6-Pad2)") (class "Default")
      (node (ref "CN6") (pin "2") (pinfunction "2_2") (pintype "unspecified"))
      (node (ref "K4") (pin "2") (pinfunction "2_2") (pintype "unspecified"))
    )
    (net (code "33") (name "Net-(CN9-Pad1)") (class "Default")
      (node (ref "CN9") (pin "1") (pinfunction "1_1") (pintype "unspecified"))
      (node (ref "K1") (pin "3") (pinfunction "3_3") (pintype "unspecified"))
    )
    (net (code "34") (name "Net-(CN9-Pad2)") (class "Default")
      (node (ref "CN9") (pin "2") (pinfunction "2_2") (pintype "unspecified"))
      (node (ref "K1") (pin "2") (pinfunction "2_2") (pintype "unspecified"))
    )
    (net (code "35") (name "Net-(D3-A)") (class "Default")
      (node (ref "D3") (pin "2") (pinfunction "A_2") (pintype "unspecified"))
      (node (ref "LD1") (pin "2") (pinfunction "A_2") (pintype "input"))
      (node (ref "LD2") (pin "2") (pinfunction "A_2") (pintype "input"))
      (node (ref "Q2") (pin "1") (pinfunction "G_1") (pintype "unspecified"))
      (node (ref "R6") (pin "2") (pinfunction "2_2") (pintype "unspecified"))
      (node (ref "U6") (pin "4") (pinfunction "VCC_4") (pintype "unspecified"))
      (node (ref "U6") (pin "8") (pinfunction "CE_8") (pintype "unspecified"))
    )
    (net (code "36") (name "Net-(D4-A)") (class "Default")
      (node (ref "D4") (pin "2") (pinfunction "A_2") (pintype "unspecified"))
      (node (ref "K1") (pin "1") (pinfunction "1_1") (pintype "unspecified"))
      (node (ref "Q5") (pin "3") (pinfunction "C_3") (pintype "input"))
    )
    (net (code "37") (name "Net-(D5-A)") (class "Default")
      (node (ref "D5") (pin "2") (pinfunction "A_2") (pintype "unspecified"))
      (node (ref "K2") (pin "1") (pinfunction "1_1") (pintype "unspecified"))
      (node (ref "Q6") (pin "3") (pinfunction "C_3") (pintype "input"))
    )
    (net (code "38") (name "Net-(D6-A)") (class "Default")
      (node (ref "D6") (pin "2") (pinfunction "A_2") (pintype "unspecified"))
      (node (ref "K3") (pin "1") (pinfunction "1_1") (pintype "unspecified"))
      (node (ref "Q7") (pin "3") (pinfunction "C_3") (pintype "input"))
    )
    (net (code "39") (name "Net-(D7-A)") (class "Default")
      (node (ref "D7") (pin "2") (pinfunction "A_2") (pintype "unspecified"))
      (node (ref "K4") (pin "1") (pinfunction "1_1") (pintype "unspecified"))
      (node (ref "Q8") (pin "3") (pinfunction "C_3") (pintype "input"))
    )
    (net (code "40") (name "Net-(LD1-C)") (class "Default")
      (node (ref "LD1") (pin "1") (pinfunction "C_1") (pintype "input"))
      (node (ref "R5") (pin "2") (pinfunction "2_2") (pintype "input"))
    )
    (net (code "41") (name "Net-(LD2-C)") (class "Default")
      (node (ref "LD2") (pin "1") (pinfunction "C_1") (pintype "input"))
      (node (ref "R2") (pin "2") (pinfunction "2_2") (pintype "input"))
    )
    (net (code "42") (name "Net-(Q3-B)") (class "Default")
      (node (ref "Q3") (pin "1") (pinfunction "B_1") (pintype "input"))
      (node (ref "R10") (pin "1") (pinfunction "1_1") (pintype "input"))
    )
    (net (code "43") (name "Net-(Q3-E)") (class "Default")
      (node (ref "Q3") (pin "2") (pinfunction "E_2") (pintype "input"))
      (node (ref "R11") (pin "2") (pinfunction "2_2") (pintype "input"))
      (node (ref "U4") (pin "14") (pinfunction "RTS#_14") (pintype "unspecified"))
    )
    (net (code "44") (name "Net-(Q4-B)") (class "Default")
      (node (ref "Q4") (pin "1") (pinfunction "B_1") (pintype "input"))
      (node (ref "R11") (pin "1") (pinfunction "1_1") (pintype "input"))
    )
    (net (code "45") (name "Net-(Q4-E)") (class "Default")
      (node (ref "Q4") (pin "2") (pinfunction "E_2") (pintype "input"))
      (node (ref "R10") (pin "2") (pinfunction "2_2") (pintype "input"))
      (node (ref "U4") (pin "13") (pinfunction "DTR#_13") (pintype "unspecified"))
    )
    (net (code "46") (name "Net-(Q5-B)") (class "Default")
      (node (ref "Q5") (pin "1") (pinfunction "B_1") (pintype "input"))
      (node (ref "R21") (pin "1") (pinfunction "1_1") (pintype "input"))
      (node (ref "R22") (pin "2") (pinfunction "2_2") (pintype "input"))
    )
    (net (code "47") (name "Net-(Q6-B)") (class "Default")
      (node (ref "Q6") (pin "1") (pinfunction "B_1") (pintype "input"))
      (node (ref "R23") (pin "1") (pinfunction "1_1") (pintype "input"))
      (node (ref "R24") (pin "2") (pinfunction "2_2") (pintype "input"))
    )
    (net (code "48") (name "Net-(Q7-B)") (class "Default")
      (node (ref "Q7") (pin "1") (pinfunction "B_1") (pintype "input"))
      (node (ref "R25") (pin "1") (pinfunction "1_1") (pintype "input"))
      (node (ref "R26") (pin "2") (pinfunction "2_2") (pintype "input"))
    )
    (net (code "49") (name "Net-(Q8-B)") (class "Default")
      (node (ref "Q8") (pin "1") (pinfunction "B_1") (pintype "input"))
      (node (ref "R27") (pin "1") (pinfunction "1_1") (pintype "input"))
      (node (ref "R28") (pin "2") (pinfunction "2_2") (pintype "input"))
    )
    (net (code "50") (name "Net-(R32-Pad2)") (class "Default")
      (node (ref "R32") (pin "2") (pinfunction "2_2") (pintype "input"))
      (node (ref "R33") (pin "2") (pinfunction "2_2") (pintype "input"))
    )
    (net (code "51") (name "Net-(TF1-CD{slash}DAT3)") (class "Default")
      (node (ref "R15") (pin "1") (pinfunction "1_1") (pintype "input"))
      (node (ref "TF1") (pin "2") (pinfunction "CD/DAT3_2") (pintype "unspecified"))
    )
    (net (code "52") (name "Net-(TF1-CLK)") (class "Default")
      (node (ref "R17") (pin "1") (pinfunction "1_1") (pintype "input"))
      (node (ref "TF1") (pin "5") (pinfunction "CLK_5") (pintype "unspecified"))
    )
    (net (code "53") (name "Net-(TF1-DAT0)") (class "Default")
      (node (ref "R20") (pin "1") (pinfunction "1_1") (pintype "input"))
      (node (ref "TF1") (pin "7") (pinfunction "DAT0_7") (pintype "unspecified"))
    )
    (net (code "54") (name "Net-(TF1-DAT1)") (class "Default")
      (node (ref "R19") (pin "1") (pinfunction "1_1") (pintype "input"))
      (node (ref "TF1") (pin "8") (pinfunction "DAT1_8") (pintype "unspecified"))
    )
    (net (code "55") (name "Net-(TF1-DAT2)") (class "Default")
      (node (ref "R14") (pin "1") (pinfunction "1_1") (pintype "input"))
      (node (ref "TF1") (pin "1") (pinfunction "DAT2_1") (pintype "unspecified"))
    )
    (net (code "56") (name "Net-(TF1-VDD)") (class "Default")
      (node (ref "C15") (pin "1") (pinfunction "1_1") (pintype "input"))
      (node (ref "FB1") (pin "2") (pinfunction "2_2") (pintype "unspecified"))
      (node (ref "TF1") (pin "4") (pinfunction "VDD_4") (pintype "unspecified"))
    )
    (net (code "57") (name "Net-(U6-CHRG#)") (class "Default")
      (node (ref "R2") (pin "1") (pinfunction "1_1") (pintype "input"))
      (node (ref "U6") (pin "7") (pinfunction "CHRG#_7") (pintype "unspecified"))
    )
    (net (code "58") (name "Net-(U6-PROG)") (class "Default")
      (node (ref "R7") (pin "1") (pinfunction "1_1") (pintype "input"))
      (node (ref "U6") (pin "2") (pinfunction "PROG_2") (pintype "unspecified"))
    )
    (net (code "59") (name "Net-(U6-STDBY#)") (class "Default")
      (node (ref "R5") (pin "1") (pinfunction "1_1") (pintype "input"))
      (node (ref "U6") (pin "6") (pinfunction "STDBY#_6") (pintype "unspecified"))
    )
    (net (code "60") (name "Net-(U8-DI)") (class "Default")
      (node (ref "R30") (pin "1") (pinfunction "1_1") (pintype "input"))
      (node (ref "U8") (pin "4") (pinfunction "DI_4") (pintype "unspecified"))
    )
    (net (code "61") (name "Net-(U8-R0)") (class "Default")
      (node (ref "R29") (pin "1") (pinfunction "1_1") (pintype "input"))
      (node (ref "U8") (pin "1") (pinfunction "R0_1") (pintype "unspecified"))
    )
    (net (code "62") (name "Net-(U9-1Y)") (class "Default")
      (node (ref "CN8") (pin "1") (pinfunction "1_1") (pintype "unspecified"))
      (node (ref "U9") (pin "3") (pinfunction "1Y_3") (pintype "unspecified"))
    )
    (net (code "63") (name "Net-(U9-2Y)") (class "Default")
      (node (ref "CN8") (pin "3") (pinfunction "3_3") (pintype "unspecified"))
      (node (ref "U9") (pin "6") (pinfunction "2Y_6") (pintype "unspecified"))
    )
    (net (code "64") (name "Net-(U9-3Y)") (class "Default")
      (node (ref "CN8") (pin "5") (pinfunction "5_5") (pintype "unspecified"))
      (node (ref "U9") (pin "8") (pinfunction "3Y_8") (pintype "unspecified"))
    )
    (net (code "65") (name "Net-(U9-4Y)") (class "Default")
      (node (ref "CN8") (pin "7") (pinfunction "7_7") (pintype "unspecified"))
      (node (ref "U9") (pin "11") (pinfunction "4Y_11") (pintype "unspecified"))
    )
    (net (code "66") (name "Net-(U9-VCC)") (class "Default")
      (node (ref "C21") (pin "2") (pinfunction "2_2") (pintype "input"))
      (node (ref "C22") (pin "2") (pinfunction "2_2") (pintype "input"))
      (node (ref "R40") (pin "1") (pinfunction "1_1") (pintype "input"))
      (node (ref "R41") (pin "1") (pinfunction "1_1") (pintype "input"))
      (node (ref "U9") (pin "14") (pinfunction "VCC_14") (pintype "unspecified"))
    )
    (net (code "67") (name "RS485+") (class "Default")
      (node (ref "CN10") (pin "2") (pinfunction "2_2") (pintype "unspecified"))
      (node (ref "R33") (pin "1") (pinfunction "1_1") (pintype "input"))
      (node (ref "U8") (pin "6") (pinfunction "A_6") (pintype "unspecified"))
    )
    (net (code "68") (name "RS485-") (class "Default")
      (node (ref "CN10") (pin "1") (pinfunction "1_1") (pintype "unspecified"))
      (node (ref "R32") (pin "1") (pinfunction "1_1") (pintype "input"))
      (node (ref "U8") (pin "7") (pinfunction "B_7") (pintype "unspecified"))
    )
    (net (code "69") (name "RXD0") (class "Default")
      (node (ref "U3") (pin "34") (pinfunction "RXD0_34") (pintype "unspecified"))
      (node (ref "U4") (pin "2") (pinfunction "TXD_2") (pintype "unspecified"))
    )
    (net (code "70") (name "TXD0") (class "Default")
      (node (ref "U3") (pin "35") (pinfunction "TXD0_35") (pintype "unspecified"))
      (node (ref "U4") (pin "3") (pinfunction "RXD_3") (pintype "unspecified"))
    )
    (net (code "71") (name "USR_LED") (class "Default")
      (node (ref "U3") (pin "14") (pinfunction "IO12_14") (pintype "unspecified"))
    )
    (net (code "72") (name "VBAT") (class "Default")
      (node (ref "C5") (pin "2") (pinfunction "2_2") (pintype "input"))
      (node (ref "C6") (pin "2") (pinfunction "2_2") (pintype "input"))
      (node (ref "CN2") (pin "1") (pinfunction "1_1") (pintype "unspecified"))
      (node (ref "Q2") (pin "3") (pinfunction "D_3") (pintype "unspecified"))
      (node (ref "R36") (pin "2") (pinfunction "2_2") (pintype "input"))
      (node (ref "U6") (pin "5") (pinfunction "BAT_5") (pintype "unspecified"))
    )
    (net (code "73") (name "VBUS") (class "Default")
      (node (ref "CN3") (pin "A4") (pinfunction "VBUS_A4") (pintype "input"))
      (node (ref "CN3") (pin "A9") (pinfunction "VBUS_A9") (pintype "input"))
      (node (ref "CN3") (pin "B4") (pinfunction "VBUS_B4") (pintype "input"))
      (node (ref "CN3") (pin "B9") (pinfunction "VBUS_B9") (pintype "input"))
      (node (ref "Q1") (pin "3") (pinfunction "D_3") (pintype "unspecified"))
    )
    (net (code "74") (name "VDC") (class "Default")
      (node (ref "D3") (pin "1") (pinfunction "C_1") (pintype "unspecified"))
      (node (ref "Q2") (pin "2") (pinfunction "S_2") (pintype "unspecified"))
    )
    (net (code "75") (name "VDD") (class "Default")
      (node (ref "C12") (pin "1") (pinfunction "1_1") (pintype "input"))
      (node (ref "C13") (pin "2") (pinfunction "2_2") (pintype "input"))
      (node (ref "C16") (pin "1") (pinfunction "1_1") (pintype "input"))
      (node (ref "C23") (pin "1") (pinfunction "1_1") (pintype "input"))
      (node (ref "CN8") (pin "6") (pinfunction "6_6") (pintype "unspecified"))
      (node (ref "FB1") (pin "1") (pinfunction "1_1") (pintype "unspecified"))
      (node (ref "R12") (pin "2") (pinfunction "2_2") (pintype "input"))
      (node (ref "R13") (pin "2") (pinfunction "2_2") (pintype "input"))
      (node (ref "R14") (pin "2") (pinfunction "2_2") (pintype "input"))
      (node (ref "R15") (pin "2") (pinfunction "2_2") (pintype "input"))
      (node (ref "R16") (pin "2") (pinfunction "2_2") (pintype "input"))
      (node (ref "R18") (pin "2") (pinfunction "2_2") (pintype "input"))
      (node (ref "R19") (pin "2") (pinfunction "2_2") (pintype "input"))
      (node (ref "R38") (pin "2") (pinfunction "2_2") (pintype "input"))
      (node (ref "R39") (pin "2") (pinfunction "2_2") (pintype "input"))
      (node (ref "R41") (pin "2") (pinfunction "2_2") (pintype "input"))
      (node (ref "R43") (pin "2") (pinfunction "2_2") (pintype "input"))
      (node (ref "U10") (pin "3") (pinfunction "VDD_3") (pintype "input"))
      (node (ref "U3") (pin "2") (pinfunction "3V3_2") (pintype "unspecified"))
      (node (ref "U4") (pin "16") (pinfunction "VCC_16") (pintype "unspecified"))
      (node (ref "U4") (pin "4") (pinfunction "V3_4") (pintype "unspecified"))
      (node (ref "U8") (pin "8") (pinfunction "VCC_8") (pintype "unspecified"))
    )
    (net (code "76") (name "VEXT") (class "Default")
      (node (ref "C1") (pin "1") (pinfunction "1_1") (pintype "input"))
      (node (ref "C2") (pin "1") (pinfunction "1_1") (pintype "input"))
      (node (ref "C3") (pin "2") (pinfunction "2_2") (pintype "input"))
      (node (ref "C4") (pin "2") (pinfunction "2_2") (pintype "input"))
      (node (ref "CN8") (pin "2") (pinfunction "2_2") (pintype "unspecified"))
      (node (ref "D1") (pin "1") (pinfunction "C_1") (pintype "unspecified"))
      (node (ref "D2") (pin "1") (pinfunction "1_1") (pintype "unspecified"))
      (node (ref "D4") (pin "1") (pinfunction "C_1") (pintype "unspecified"))
      (node (ref "D5") (pin "1") (pinfunction "C_1") (pintype "unspecified"))
      (node (ref "D6") (pin "1") (pinfunction "C_1") (pintype "unspecified"))
      (node (ref "D7") (pin "1") (pinfunction "C_1") (pintype "unspecified"))
      (node (ref "K1") (pin "4") (pinfunction "4_4") (pintype "unspecified"))
      (node (ref "K2") (pin "4") (pinfunction "4_4") (pintype "unspecified"))
      (node (ref "K3") (pin "4") (pinfunction "4_4") (pintype "unspecified"))
      (node (ref "K4") (pin "4") (pinfunction "4_4") (pintype "unspecified"))
      (node (ref "Q1") (pin "2") (pinfunction "S_2") (pintype "unspecified"))
      (node (ref "R34") (pin "1") (pinfunction "1_1") (pintype "input"))
      (node (ref "R40") (pin "2") (pinfunction "2_2") (pintype "input"))
      (node (ref "R6") (pin "1") (pinfunction "1_1") (pintype "unspecified"))
    )
    (net (code "77") (name "V_EXT") (class "Default")
      (node (ref "CN1") (pin "1") (pinfunction "1_1") (pintype "unspecified"))
      (node (ref "D1") (pin "2") (pinfunction "A_2") (pintype "unspecified"))
      (node (ref "DC1") (pin "1") (pinfunction "4_1") (pintype "input"))
      (node (ref "Q1") (pin "1") (pinfunction "G_1") (pintype "unspecified"))
      (node (ref "R1") (pin "2") (pinfunction "2_2") (pintype "input"))
    )
    (net (code "78") (name "unconnected-(C7-Pad1)") (class "Default")
      (node (ref "C7") (pin "1") (pinfunction "1_1") (pintype "input"))
    )
    (net (code "79") (name "unconnected-(C7-Pad2)") (class "Default")
      (node (ref "C7") (pin "2") (pinfunction "2_2") (pintype "input"))
    )
    (net (code "80") (name "unconnected-(C8-Pad1)") (class "Default")
      (node (ref "C8") (pin "1") (pinfunction "1_1") (pintype "input"))
    )
    (net (code "81") (name "unconnected-(C8-Pad2)") (class "Default")
      (node (ref "C8") (pin "2") (pinfunction "2_2") (pintype "input"))
    )
    (net (code "82") (name "unconnected-(C9-Pad1)") (class "Default")
      (node (ref "C9") (pin "1") (pinfunction "1_1") (pintype "input"))
    )
    (net (code "83") (name "unconnected-(C9-Pad2)") (class "Default")
      (node (ref "C9") (pin "2") (pinfunction "2_2") (pintype "input"))
    )
    (net (code "84") (name "unconnected-(C10-Pad1)") (class "Default")
      (node (ref "C10") (pin "1") (pinfunction "1_1") (pintype "input"))
    )
    (net (code "85") (name "unconnected-(C10-Pad2)") (class "Default")
      (node (ref "C10") (pin "2") (pinfunction "2_2") (pintype "input"))
    )
    (net (code "86") (name "unconnected-(C11-Pad1)") (class "Default")
      (node (ref "C11") (pin "1") (pinfunction "1_1") (pintype "input"))
    )
    (net (code "87") (name "unconnected-(C11-Pad2)") (class "Default")
      (node (ref "C11") (pin "2") (pinfunction "2_2") (pintype "input"))
    )
    (net (code "88") (name "unconnected-(CN3-SBUS1-PadA8)") (class "Default")
      (node (ref "CN3") (pin "A8") (pinfunction "SBUS1_A8") (pintype "input+no_connect"))
    )
    (net (code "89") (name "unconnected-(CN3-SBUS2-PadB8)") (class "Default")
      (node (ref "CN3") (pin "B8") (pinfunction "SBUS2_B8") (pintype "input+no_connect"))
    )
    (net (code "90") (name "unconnected-(L1-Pad1)") (class "Default")
      (node (ref "L1") (pin "1") (pinfunction "1_1") (pintype "unspecified"))
    )
    (net (code "91") (name "unconnected-(L1-Pad2)") (class "Default")
      (node (ref "L1") (pin "2") (pinfunction "2_2") (pintype "unspecified"))
    )
    (net (code "92") (name "unconnected-(LD3-A-Pad2)") (class "Default")
      (node (ref "LD3") (pin "2") (pinfunction "A_2") (pintype "input"))
    )
    (net (code "93") (name "unconnected-(LD3-C-Pad1)") (class "Default")
      (node (ref "LD3") (pin "1") (pinfunction "C_1") (pintype "input"))
    )
    (net (code "94") (name "unconnected-(R8-Pad1)") (class "Default")
      (node (ref "R8") (pin "1") (pinfunction "1_1") (pintype "input"))
    )
    (net (code "95") (name "unconnected-(R8-Pad2)") (class "Default")
      (node (ref "R8") (pin "2") (pinfunction "2_2") (pintype "input"))
    )
    (net (code "96") (name "unconnected-(R9-Pad1)") (class "Default")
      (node (ref "R9") (pin "1") (pinfunction "1_1") (pintype "input"))
    )
    (net (code "97") (name "unconnected-(R9-Pad2)") (class "Default")
      (node (ref "R9") (pin "2") (pinfunction "2_2") (pintype "input"))
    )
    (net (code "98") (name "unconnected-(R42-Pad1)") (class "Default")
      (node (ref "R42") (pin "1") (pinfunction "1_1") (pintype "input"))
    )
    (net (code "99") (name "unconnected-(R42-Pad2)") (class "Default")
      (node (ref "R42") (pin "2") (pinfunction "2_2") (pintype "input"))
    )
    (net (code "100") (name "unconnected-(TF1-CD-Pad9)") (class "Default")
      (node (ref "TF1") (pin "9") (pinfunction "CD_9") (pintype "unspecified+no_connect"))
    )
    (net (code "101") (name "unconnected-(U3-CLK-Pad20)") (class "Default")
      (node (ref "U3") (pin "20") (pinfunction "CLK_20") (pintype "unspecified+no_connect"))
    )
    (net (code "102") (name "unconnected-(U3-CMD-Pad19)") (class "Default")
      (node (ref "U3") (pin "19") (pinfunction "CMD_19") (pintype "unspecified+no_connect"))
    )
    (net (code "103") (name "unconnected-(U3-IO27-Pad12)") (class "Default")
      (node (ref "U3") (pin "12") (pinfunction "IO27_12") (pintype "unspecified+no_connect"))
    )
    (net (code "104") (name "unconnected-(U3-NC-Pad32)") (class "Default")
      (node (ref "U3") (pin "32") (pinfunction "NC_32") (pintype "unspecified+no_connect"))
    )
    (net (code "105") (name "unconnected-(U3-SD0-Pad21)") (class "Default")
      (node (ref "U3") (pin "21") (pinfunction "SD0_21") (pintype "unspecified+no_connect"))
    )
    (net (code "106") (name "unconnected-(U3-SD1-Pad22)") (class "Default")
      (node (ref "U3") (pin "22") (pinfunction "SD1_22") (pintype "unspecified+no_connect"))
    )
    (net (code "107") (name "unconnected-(U3-SD2-Pad17)") (class "Default")
      (node (ref "U3") (pin "17") (pinfunction "SD2_17") (pintype "unspecified+no_connect"))
    )
    (net (code "108") (name "unconnected-(U3-SD3-Pad18)") (class "Default")
      (node (ref "U3") (pin "18") (pinfunction "SD3_18") (pintype "unspecified+no_connect"))
    )
    (net (code "109") (name "unconnected-(U3-SENSOR_VN-Pad5)") (class "Default")
      (node (ref "U3") (pin "5") (pinfunction "SENSOR_VN_5") (pintype "unspecified+no_connect"))
    )
    (net (code "110") (name "unconnected-(U3-SENSOR_VP-Pad4)") (class "Default")
      (node (ref "U3") (pin "4") (pinfunction "SENSOR_VP_4") (pintype "unspecified+no_connect"))
    )
    (net (code "111") (name "unconnected-(U4-CTS#-Pad9)") (class "Default")
      (node (ref "U4") (pin "9") (pinfunction "CTS#_9") (pintype "unspecified+no_connect"))
    )
    (net (code "112") (name "unconnected-(U4-DCD#-Pad12)") (class "Default")
      (node (ref "U4") (pin "12") (pinfunction "DCD#_12") (pintype "unspecified+no_connect"))
    )
    (net (code "113") (name "unconnected-(U4-DSR#-Pad10)") (class "Default")
      (node (ref "U4") (pin "10") (pinfunction "DSR#_10") (pintype "unspecified+no_connect"))
    )
    (net (code "114") (name "unconnected-(U4-NC.-Pad7)") (class "Default")
      (node (ref "U4") (pin "7") (pinfunction "NC._7") (pintype "unspecified+no_connect"))
    )
    (net (code "115") (name "unconnected-(U4-OUT#-Pad8)") (class "Default")
      (node (ref "U4") (pin "8") (pinfunction "OUT#_8") (pintype "unspecified+no_connect"))
    )
    (net (code "116") (name "unconnected-(U4-R232-Pad15)") (class "Default")
      (node (ref "U4") (pin "15") (pinfunction "R232_15") (pintype "unspecified+no_connect"))
    )
    (net (code "117") (name "unconnected-(U4-RI#-Pad11)") (class "Default")
      (node (ref "U4") (pin "11") (pinfunction "RI#_11") (pintype "unspecified+no_connect"))
    )
  )
)
